# charger.net
KiCad netlist of a schematic drawn in EAGLE
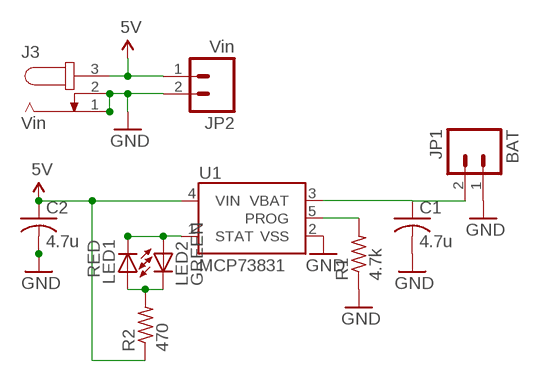
[diagram p0: schematic, sheet 1]

(export (version "E")
  (design (tool "Eeschema 10.0.6"))
  (components
    (comp (ref "C1")
      (value "4.7u")
      (footprint "eagle-import:C0805")
      (libsource (lib "eagle-import") (part "C-USC0805"))
    )
    (comp (ref "C2")
      (value "4.7u")
      (footprint "eagle-import:C0805")
      (libsource (lib "eagle-import") (part "C-USC0805"))
    )
    (comp (ref "J3")
      (value "Vin")
      (footprint "eagle-import:SPC4077")
      (libsource (lib "eagle-import") (part "JACK-PLUG0"))
    )
    (comp (ref "JP1")
      (value "BAT")
      (footprint "eagle-import:JST-2-PTH")
      (libsource (lib "eagle-import") (part "M02JST-PTH-2"))
    )
    (comp (ref "JP2")
      (value "Vin")
      (footprint "eagle-import:1X02_LOCK_LONGPADS")
      (libsource (lib "eagle-import") (part "M02LOCK_LONGPADS"))
    )
    (comp (ref "LED1")
      (value "RED")
      (footprint "eagle-import:SML0805")
      (libsource (lib "eagle-import") (part "LEDSML0805"))
    )
    (comp (ref "LED2")
      (value "GREEN")
      (footprint "eagle-import:SML0805")
      (libsource (lib "eagle-import") (part "LEDSML0805"))
    )
    (comp (ref "R1")
      (value "4.7k")
      (footprint "eagle-import:M1206")
      (libsource (lib "eagle-import") (part "R-US_M1206"))
    )
    (comp (ref "R2")
      (value "470")
      (footprint "eagle-import:M1206")
      (libsource (lib "eagle-import") (part "R-US_M1206"))
    )
    (comp (ref "U1")
      (value "MCP73831")
      (footprint "eagle-import:SOT23-5")
      (libsource (lib "eagle-import") (part "MCP73831"))
    )
  )
  (nets
    (net (code "1") (name "5V") (class "Default")
      (node (ref "C2") (pin "1") (pinfunction "1_1") (pintype "passive"))
      (node (ref "J3") (pin "3") (pinfunction "3_3") (pintype "passive"))
      (node (ref "JP2") (pin "1") (pinfunction "1_1") (pintype "passive"))
      (node (ref "R2") (pin "1") (pinfunction "1_1") (pintype "passive"))
      (node (ref "U1") (pin "4") (pinfunction "VIN_4") (pintype "power_in"))
    )
    (net (code "2") (name "GND") (class "Default")
      (node (ref "C1") (pin "2") (pinfunction "2_2") (pintype "passive"))
      (node (ref "C2") (pin "2") (pinfunction "2_2") (pintype "passive"))
      (node (ref "J3") (pin "1") (pinfunction "1_1") (pintype "passive"))
      (node (ref "J3") (pin "2") (pinfunction "2_2") (pintype "passive"))
      (node (ref "JP1") (pin "1") (pinfunction "1_1") (pintype "passive"))
      (node (ref "JP2") (pin "2") (pinfunction "2_2") (pintype "passive"))
      (node (ref "R1") (pin "1") (pinfunction "1_1") (pintype "passive"))
      (node (ref "U1") (pin "2") (pinfunction "VSS_2") (pintype "power_in"))
    )
    (net (code "3") (name "Net-(LED1-PadA)") (class "Default")
      (node (ref "LED1") (pin "A") (pinfunction "A_A") (pintype "passive"))
      (node (ref "LED2") (pin "C") (pinfunction "C_C") (pintype "passive"))
      (node (ref "R2") (pin "2") (pinfunction "2_2") (pintype "passive"))
    )
    (net (code "4") (name "Net-(U1-PROG)") (class "Default")
      (node (ref "R1") (pin "2") (pinfunction "2_2") (pintype "passive"))
      (node (ref "U1") (pin "5") (pinfunction "PROG_5") (pintype "input"))
    )
    (net (code "5") (name "Net-(U1-STAT)") (class "Default")
      (node (ref "LED1") (pin "C") (pinfunction "C_C") (pintype "passive"))
      (node (ref "LED2") (pin "A") (pinfunction "A_A") (pintype "passive"))
      (node (ref "U1") (pin "1") (pinfunction "STAT_1") (pintype "output"))
    )
    (net (code "6") (name "Net-(U1-VBAT)") (class "Default")
      (node (ref "C1") (pin "1") (pinfunction "1_1") (pintype "passive"))
      (node (ref "JP1") (pin "2") (pinfunction "2_2") (pintype "passive"))
      (node (ref "U1") (pin "3") (pinfunction "VBAT_3") (pintype "power_in"))
    )
  )
)
